# Sensy_Boi_sch.net
KiCad netlist of a schematic drawn in Altium Designer
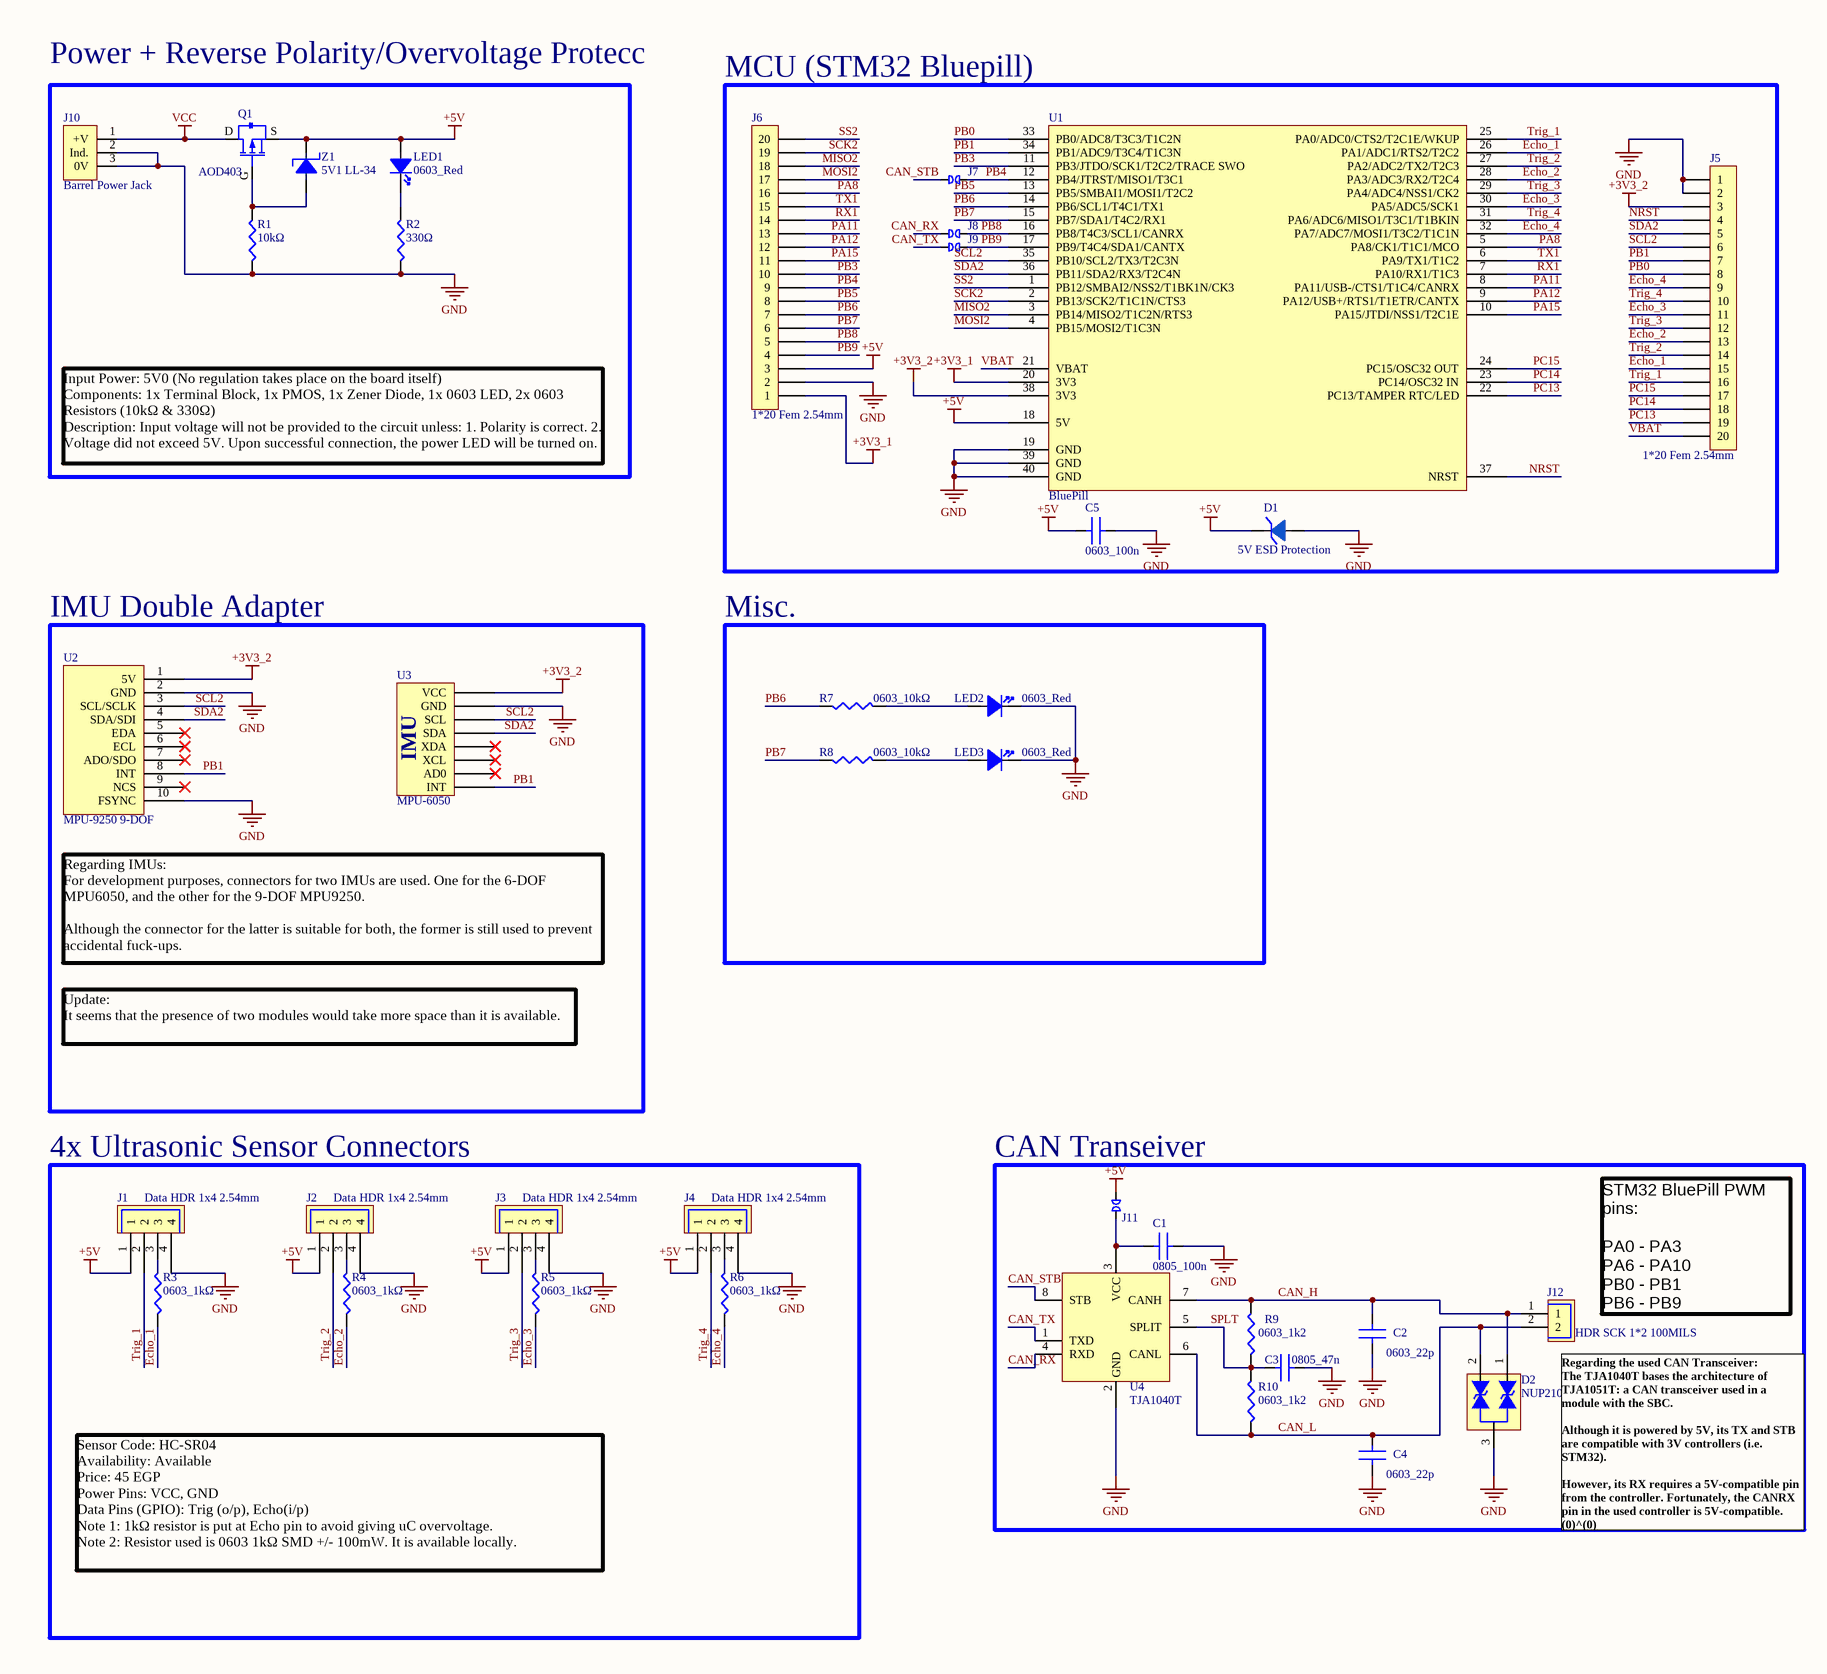
[diagram p0: Sensy_Boi_sch.SchDoc, left]

(export (version "E")
  (design (tool "Eeschema 10.0.6"))
  (components
    (comp (ref "C1")
      (value "0805_100n")
      (footprint "C0805 - 0.1uf")
      (fields (field (name "TOLERANCE") "10%") (field (name "VOLTAGE") "25V"))
      (libsource (lib "TimerSMD_Components") (part "C2012X5R1E105K125AA"))
    )
    (comp (ref "C2")
      (value "0603_22p")
      (footprint "0603_CAP")
      (libsource (lib "TimerSMD_Components") (part "0603 Capacitor"))
    )
    (comp (ref "C3")
      (value "0805_47n")
      (footprint "C0805 - 0.1uf")
      (fields (field (name "TOLERANCE") "10%") (field (name "VOLTAGE") "25V"))
      (libsource (lib "TimerSMD_Components") (part "C2012X5R1E105K125AA"))
    )
    (comp (ref "C4")
      (value "0603_22p")
      (footprint "0603_CAP")
      (libsource (lib "TimerSMD_Components") (part "0603 Capacitor"))
    )
    (comp (ref "C5")
      (value "0603_100n")
      (footprint "0603_CAP")
      (libsource (lib "TimerSMD_Components") (part "0603 Capacitor"))
    )
    (comp (ref "D1")
      (value "5V ESD Protection")
      (footprint "D0-214AA")
      (libsource (lib "TimerSMD_Components") (part "SMBJ5.0A"))
    )
    (comp (ref "D2")
      (value "NUP2105L")
      (footprint "SO-23")
      (description "ESD Protection Dual Diode for CAN Bus Line Protection")
      (libsource (lib "TimerSMD_Components") (part "NUP2105L"))
    )
    (comp (ref "J1")
      (value "Data HDR 1x4 2.54mm")
      (footprint "DHDR_1x4_2.54mm")
      (description "MTA-100 Series, 2.54mm Pitch 4 Way 1 RowStraight PCB Header, Solder Term, 5A")
      (libsource (lib "CAD_Symbols") (part "4-Pin Data Connector"))
    )
    (comp (ref "J2")
      (value "Data HDR 1x4 2.54mm")
      (footprint "DHDR_1x4_2.54mm")
      (description "MTA-100 Series, 2.54mm Pitch 4 Way 1 RowStraight PCB Header, Solder Term, 5A")
      (libsource (lib "CAD_Symbols") (part "4-Pin Data Connector"))
    )
    (comp (ref "J3")
      (value "Data HDR 1x4 2.54mm")
      (footprint "DHDR_1x4_2.54mm")
      (description "MTA-100 Series, 2.54mm Pitch 4 Way 1 RowStraight PCB Header, Solder Term, 5A")
      (libsource (lib "CAD_Symbols") (part "4-Pin Data Connector"))
    )
    (comp (ref "J4")
      (value "Data HDR 1x4 2.54mm")
      (footprint "DHDR_1x4_2.54mm")
      (description "MTA-100 Series, 2.54mm Pitch 4 Way 1 RowStraight PCB Header, Solder Term, 5A")
      (libsource (lib "CAD_Symbols") (part "4-Pin Data Connector"))
    )
    (comp (ref "J5")
      (value "1*20 Fem 2.54mm")
      (footprint "20*1 FEM 2.54mm")
      (libsource (lib "") (part "1*20 Fem 2.54mm_1"))
    )
    (comp (ref "J6")
      (value "1*20 Fem 2.54mm")
      (footprint "20*1 FEM 2.54mm")
      (libsource (lib "CAD_Symbols") (part "1*20 Fem 2.54mm"))
    )
    (comp (ref "J7")
      (value "Jumper Pads")
      (footprint "JMP")
      (libsource (lib "TimerSMD_Components") (part "Jumper Pads"))
    )
    (comp (ref "J8")
      (value "Jumper Pads")
      (footprint "JMP")
      (libsource (lib "TimerSMD_Components") (part "Jumper Pads"))
    )
    (comp (ref "J9")
      (value "Jumper Pads")
      (footprint "JMP")
      (libsource (lib "TimerSMD_Components") (part "Jumper Pads"))
    )
    (comp (ref "J10")
      (value "Barrel Power Jack")
      (footprint "pwr_Jack")
      (description "DC-Power Socket 12V 5A 2, 1mm Solder Eyel")
      (libsource (lib "CAD_Symbols") (part "Con-Jack"))
    )
    (comp (ref "J11")
      (value "Jumper Pads")
      (footprint "JMP")
      (libsource (lib "TimerSMD_Components") (part "Jumper Pads"))
    )
    (comp (ref "J12")
      (value "HDR SCK 1*2 100MILS")
      (footprint "DHDR 1*2 2,54MM")
      (description "Conn Shrouded Header HDR 2 POS 2.54mm Solder ST Thru-Hole")
      (libsource (lib "CAD_Symbols") (part "2-Pin Data Connector"))
    )
    (comp (ref "LED1")
      (value "0603_Red")
      (footprint "0603_LED")
      (libsource (lib "TimerSMD_Components") (part "0603LED"))
    )
    (comp (ref "LED2")
      (value "0603_Red")
      (footprint "0603_LED")
      (libsource (lib "TimerSMD_Components") (part "0603LED"))
    )
    (comp (ref "LED3")
      (value "0603_Red")
      (footprint "0603_LED")
      (libsource (lib "TimerSMD_Components") (part "0603LED"))
    )
    (comp (ref "Q1")
      (value "AOD403")
      (footprint "DPAK")
      (description "MOSFET Transistor P-Channel 30V 15A 3.5V @ 250uA 6mΩ @ 20A,20V 2.5W TO-252-2(DPAK)")
      (libsource (lib "TimerSMD_Components") (part "AOD403"))
    )
    (comp (ref "R1")
      (value "10kΩ")
      (footprint "0603_CAP")
      (libsource (lib "TimerSMD_Components") (part "0603 Resistor"))
    )
    (comp (ref "R2")
      (value "330Ω")
      (footprint "0603_CAP")
      (libsource (lib "TimerSMD_Components") (part "0603 Resistor"))
    )
    (comp (ref "R3")
      (value "0603_1kΩ")
      (footprint "0603_CAP")
      (description "1k +/- 1 100mW")
      (libsource (lib "TimerSMD_Components") (part "0603 Resistor"))
    )
    (comp (ref "R4")
      (value "0603_1kΩ")
      (footprint "0603_CAP")
      (description "1k +/- 1 100mW")
      (libsource (lib "TimerSMD_Components") (part "0603 Resistor"))
    )
    (comp (ref "R5")
      (value "0603_1kΩ")
      (footprint "0603_CAP")
      (description "1k +/- 1 100mW")
      (libsource (lib "TimerSMD_Components") (part "0603 Resistor"))
    )
    (comp (ref "R6")
      (value "0603_1kΩ")
      (footprint "0603_CAP")
      (description "1k +/- 1 100mW")
      (libsource (lib "TimerSMD_Components") (part "0603 Resistor"))
    )
    (comp (ref "R7")
      (value "0603_10kΩ")
      (footprint "0603_CAP")
      (libsource (lib "TimerSMD_Components") (part "0603 Resistor"))
    )
    (comp (ref "R8")
      (value "0603_10kΩ")
      (footprint "0603_CAP")
      (libsource (lib "TimerSMD_Components") (part "0603 Resistor"))
    )
    (comp (ref "R9")
      (value "0603_1k2")
      (footprint "0603_CAP")
      (libsource (lib "TimerSMD_Components") (part "0603 Resistor"))
    )
    (comp (ref "R10")
      (value "0603_1k2")
      (footprint "0603_CAP")
      (libsource (lib "TimerSMD_Components") (part "0603 Resistor"))
    )
    (comp (ref "U1")
      (value "BluePill")
      (footprint "BluePill")
      (libsource (lib "CAD_Symbols") (part "STM32 BluePill"))
    )
    (comp (ref "U2")
      (value "MPU-9250 9-DOF")
      (footprint "MPU9250")
      (libsource (lib "CAD_Symbols") (part "MPU-9250 IMU"))
    )
    (comp (ref "U3")
      (value "MPU-6050")
      (footprint "IMU")
      (libsource (lib "CAD_Symbols") (part "MPU-6050 IMU"))
    )
    (comp (ref "U4")
      (value "TJA1040T")
      (footprint "SOP8 - duplicate")
      (description "CAN Transceiver")
      (libsource (lib "TimerSMD_Components") (part "TJA1040T"))
    )
    (comp (ref "Z1")
      (value "5V1 LL-34")
      (footprint "LL-34")
      (libsource (lib "TimerSMD_Components") (part "Zener 5V1 LL-34"))
    )
  )
  (nets
    (net (code "1") (name "+3V3_1") (class "Default")
      (node (ref "J6") (pin "1") (pinfunction "1_1") (pintype "passive"))
      (node (ref "U1") (pin "20") (pinfunction "3V3_20") (pintype "passive"))
    )
    (net (code "2") (name "+3V3_2") (class "Default")
      (node (ref "J5") (pin "3") (pinfunction "3_3") (pintype "passive"))
      (node (ref "U1") (pin "38") (pinfunction "3V3_38") (pintype "passive"))
      (node (ref "U2") (pin "1") (pinfunction "5V_1") (pintype "passive"))
      (node (ref "U3") (pin "VCC") (pinfunction "VCC_VCC") (pintype "passive"))
    )
    (net (code "3") (name "+5V") (class "Default")
      (node (ref "C5") (pin "1") (pinfunction "1_1") (pintype "passive"))
      (node (ref "D1") (pin "K") (pinfunction "Cathode_K") (pintype "passive"))
      (node (ref "J1") (pin "1") (pinfunction "1_1") (pintype "passive"))
      (node (ref "J11") (pin "2") (pinfunction "2_2") (pintype "passive"))
      (node (ref "J2") (pin "1") (pinfunction "1_1") (pintype "passive"))
      (node (ref "J3") (pin "1") (pinfunction "1_1") (pintype "passive"))
      (node (ref "J4") (pin "1") (pinfunction "1_1") (pintype "passive"))
      (node (ref "J6") (pin "3") (pinfunction "3_3") (pintype "passive"))
      (node (ref "LED1") (pin "1") (pinfunction "Anode_1") (pintype "passive"))
      (node (ref "Q1") (pin "S") (pinfunction "S_S") (pintype "passive"))
      (node (ref "U1") (pin "18") (pinfunction "5V_18") (pintype "passive"))
      (node (ref "Z1") (pin "K") (pinfunction "Cathode_K") (pintype "passive"))
    )
    (net (code "4") (name "/CAN_H") (class "Default")
      (node (ref "C2") (pin "2") (pinfunction "2_2") (pintype "passive"))
      (node (ref "D2") (pin "1") (pinfunction "IN1_1") (pintype "passive"))
      (node (ref "J12") (pin "1") (pinfunction "1_1") (pintype "passive"))
      (node (ref "R9") (pin "2") (pinfunction "2_2") (pintype "passive"))
      (node (ref "U4") (pin "7") (pinfunction "CANH_7") (pintype "passive"))
    )
    (net (code "5") (name "/CAN_L") (class "Default")
      (node (ref "C4") (pin "2") (pinfunction "2_2") (pintype "passive"))
      (node (ref "D2") (pin "2") (pinfunction "IN2_2") (pintype "passive"))
      (node (ref "J12") (pin "2") (pinfunction "2_2") (pintype "passive"))
      (node (ref "R10") (pin "1") (pinfunction "1_1") (pintype "passive"))
      (node (ref "U4") (pin "6") (pinfunction "CANL_6") (pintype "passive"))
    )
    (net (code "6") (name "/CAN_RX") (class "Default")
      (node (ref "J8") (pin "1") (pinfunction "1_1") (pintype "passive"))
      (node (ref "U4") (pin "4") (pinfunction "RXD_4") (pintype "passive"))
    )
    (net (code "7") (name "/CAN_STB") (class "Default")
      (node (ref "J7") (pin "1") (pinfunction "1_1") (pintype "passive"))
      (node (ref "U4") (pin "8") (pinfunction "STB_8") (pintype "passive"))
    )
    (net (code "8") (name "/CAN_TX") (class "Default")
      (node (ref "J9") (pin "1") (pinfunction "1_1") (pintype "passive"))
      (node (ref "U4") (pin "1") (pinfunction "TXD_1") (pintype "passive"))
    )
    (net (code "9") (name "/Echo_1") (class "Default")
      (node (ref "J5") (pin "15") (pinfunction "15_15") (pintype "passive"))
      (node (ref "R3") (pin "1") (pinfunction "1_1") (pintype "passive"))
      (node (ref "U1") (pin "26") (pinfunction "PA1/ADC1/RTS2/T2C2_26") (pintype "passive"))
    )
    (net (code "10") (name "/Echo_2") (class "Default")
      (node (ref "J5") (pin "13") (pinfunction "13_13") (pintype "passive"))
      (node (ref "R4") (pin "1") (pinfunction "1_1") (pintype "passive"))
      (node (ref "U1") (pin "28") (pinfunction "PA3/ADC3/RX2/T2C4_28") (pintype "passive"))
    )
    (net (code "11") (name "/Echo_3") (class "Default")
      (node (ref "J5") (pin "11") (pinfunction "11_11") (pintype "passive"))
      (node (ref "R5") (pin "1") (pinfunction "1_1") (pintype "passive"))
      (node (ref "U1") (pin "30") (pinfunction "PA5/ADC5/SCK1_30") (pintype "passive"))
    )
    (net (code "12") (name "/Echo_4") (class "Default")
      (node (ref "J5") (pin "9") (pinfunction "9_9") (pintype "passive"))
      (node (ref "R6") (pin "1") (pinfunction "1_1") (pintype "passive"))
      (node (ref "U1") (pin "32") (pinfunction "PA7/ADC7/MOSI1/T3C2/T1C1N_32") (pintype "passive"))
    )
    (net (code "13") (name "/MISO2") (class "Default")
      (node (ref "J6") (pin "18") (pinfunction "18_18") (pintype "passive"))
      (node (ref "U1") (pin "3") (pinfunction "PB14/MISO2/T1C2N/RTS3_3") (pintype "passive"))
    )
    (net (code "14") (name "/MOSI2") (class "Default")
      (node (ref "J6") (pin "17") (pinfunction "17_17") (pintype "passive"))
      (node (ref "U1") (pin "4") (pinfunction "PB15/MOSI2/T1C3N_4") (pintype "passive"))
    )
    (net (code "15") (name "/NRST") (class "Default")
      (node (ref "J5") (pin "4") (pinfunction "4_4") (pintype "passive"))
      (node (ref "U1") (pin "37") (pinfunction "NRST_37") (pintype "passive"))
    )
    (net (code "16") (name "/PA8") (class "Default")
      (node (ref "J6") (pin "16") (pinfunction "16_16") (pintype "passive"))
      (node (ref "U1") (pin "5") (pinfunction "PA8/CK1/T1C1/MCO_5") (pintype "passive"))
    )
    (net (code "17") (name "/PA11") (class "Default")
      (node (ref "J6") (pin "13") (pinfunction "13_13") (pintype "passive"))
      (node (ref "U1") (pin "8") (pinfunction "PA11/USB-/CTS1/T1C4/CANRX_8") (pintype "passive"))
    )
    (net (code "18") (name "/PA12") (class "Default")
      (node (ref "J6") (pin "12") (pinfunction "12_12") (pintype "passive"))
      (node (ref "U1") (pin "9") (pinfunction "PA12/USB+/RTS1/T1ETR/CANTX_9") (pintype "passive"))
    )
    (net (code "19") (name "/PA15") (class "Default")
      (node (ref "J6") (pin "11") (pinfunction "11_11") (pintype "passive"))
      (node (ref "U1") (pin "10") (pinfunction "PA15/JTDI/NSS1/T2C1E_10") (pintype "passive"))
    )
    (net (code "20") (name "/PB0") (class "Default")
      (node (ref "J5") (pin "8") (pinfunction "8_8") (pintype "passive"))
      (node (ref "U1") (pin "33") (pinfunction "PB0/ADC8/T3C3/T1C2N_33") (pintype "passive"))
    )
    (net (code "21") (name "/PB1") (class "Default")
      (node (ref "J5") (pin "7") (pinfunction "7_7") (pintype "passive"))
      (node (ref "U1") (pin "34") (pinfunction "PB1/ADC9/T3C4/T1C3N_34") (pintype "passive"))
      (node (ref "U2") (pin "8") (pinfunction "INT_8") (pintype "passive"))
      (node (ref "U3") (pin "INT") (pinfunction "INT_INT") (pintype "passive"))
    )
    (net (code "22") (name "/PB3") (class "Default")
      (node (ref "J6") (pin "10") (pinfunction "10_10") (pintype "passive"))
      (node (ref "U1") (pin "11") (pinfunction "PB3/JTDO/SCK1/T2C2/TRACE_SWO_11") (pintype "passive"))
    )
    (net (code "23") (name "/PB4") (class "Default")
      (node (ref "J6") (pin "9") (pinfunction "9_9") (pintype "passive"))
      (node (ref "J7") (pin "2") (pinfunction "2_2") (pintype "passive"))
      (node (ref "U1") (pin "12") (pinfunction "PB4/JTRST/MISO1/T3C1_12") (pintype "passive"))
    )
    (net (code "24") (name "/PB5") (class "Default")
      (node (ref "J6") (pin "8") (pinfunction "8_8") (pintype "passive"))
      (node (ref "U1") (pin "13") (pinfunction "PB5/SMBAI1/MOSI1/T2C2_13") (pintype "passive"))
    )
    (net (code "25") (name "/PB6") (class "Default")
      (node (ref "J6") (pin "7") (pinfunction "7_7") (pintype "passive"))
      (node (ref "R7") (pin "2") (pinfunction "2_2") (pintype "passive"))
      (node (ref "U1") (pin "14") (pinfunction "PB6/SCL1/T4C1/TX1_14") (pintype "passive"))
    )
    (net (code "26") (name "/PB7") (class "Default")
      (node (ref "J6") (pin "6") (pinfunction "6_6") (pintype "passive"))
      (node (ref "R8") (pin "2") (pinfunction "2_2") (pintype "passive"))
      (node (ref "U1") (pin "15") (pinfunction "PB7/SDA1/T4C2/RX1_15") (pintype "passive"))
    )
    (net (code "27") (name "/PB8") (class "Default")
      (node (ref "J6") (pin "5") (pinfunction "5_5") (pintype "passive"))
      (node (ref "J8") (pin "2") (pinfunction "2_2") (pintype "passive"))
      (node (ref "U1") (pin "16") (pinfunction "PB8/T4C3/SCL1/CANRX_16") (pintype "passive"))
    )
    (net (code "28") (name "/PB9") (class "Default")
      (node (ref "J6") (pin "4") (pinfunction "4_4") (pintype "passive"))
      (node (ref "J9") (pin "2") (pinfunction "2_2") (pintype "passive"))
      (node (ref "U1") (pin "17") (pinfunction "PB9/T4C4/SDA1/CANTX_17") (pintype "passive"))
    )
    (net (code "29") (name "/PC13") (class "Default")
      (node (ref "J5") (pin "19") (pinfunction "19_19") (pintype "passive"))
      (node (ref "U1") (pin "22") (pinfunction "PC13/TAMPER_RTC/LED_22") (pintype "passive"))
    )
    (net (code "30") (name "/PC14") (class "Default")
      (node (ref "J5") (pin "18") (pinfunction "18_18") (pintype "passive"))
      (node (ref "U1") (pin "23") (pinfunction "PC14/OSC32_IN_23") (pintype "passive"))
    )
    (net (code "31") (name "/PC15") (class "Default")
      (node (ref "J5") (pin "17") (pinfunction "17_17") (pintype "passive"))
      (node (ref "U1") (pin "24") (pinfunction "PC15/OSC32_OUT_24") (pintype "passive"))
    )
    (net (code "32") (name "/RX1") (class "Default")
      (node (ref "J6") (pin "14") (pinfunction "14_14") (pintype "passive"))
      (node (ref "U1") (pin "7") (pinfunction "PA10/RX1/T1C3_7") (pintype "passive"))
    )
    (net (code "33") (name "/SCK2") (class "Default")
      (node (ref "J6") (pin "19") (pinfunction "19_19") (pintype "passive"))
      (node (ref "U1") (pin "2") (pinfunction "PB13/SCK2/T1C1N/CTS3_2") (pintype "passive"))
    )
    (net (code "34") (name "/SCL2") (class "Default")
      (node (ref "J5") (pin "6") (pinfunction "6_6") (pintype "passive"))
      (node (ref "U1") (pin "35") (pinfunction "PB10/SCL2/TX3/T2C3N_35") (pintype "passive"))
      (node (ref "U2") (pin "3") (pinfunction "SCL/SCLK_3") (pintype "passive"))
      (node (ref "U3") (pin "SCL") (pinfunction "SCL_SCL") (pintype "passive"))
    )
    (net (code "35") (name "/SDA2") (class "Default")
      (node (ref "J5") (pin "5") (pinfunction "5_5") (pintype "passive"))
      (node (ref "U1") (pin "36") (pinfunction "PB11/SDA2/RX3/T2C4N_36") (pintype "passive"))
      (node (ref "U2") (pin "4") (pinfunction "SDA/SDI_4") (pintype "passive"))
      (node (ref "U3") (pin "SDA") (pinfunction "SDA_SDA") (pintype "passive"))
    )
    (net (code "36") (name "/SPLT") (class "Default")
      (node (ref "C3") (pin "2") (pinfunction "2_2") (pintype "passive"))
      (node (ref "R10") (pin "2") (pinfunction "2_2") (pintype "passive"))
      (node (ref "R9") (pin "1") (pinfunction "1_1") (pintype "passive"))
      (node (ref "U4") (pin "5") (pinfunction "SPLIT_5") (pintype "passive"))
    )
    (net (code "37") (name "/SS2") (class "Default")
      (node (ref "J6") (pin "20") (pinfunction "20_20") (pintype "passive"))
      (node (ref "U1") (pin "1") (pinfunction "PB12/SMBAI2/NSS2/T1BK1N/CK3_1") (pintype "passive"))
    )
    (net (code "38") (name "/TX1") (class "Default")
      (node (ref "J6") (pin "15") (pinfunction "15_15") (pintype "passive"))
      (node (ref "U1") (pin "6") (pinfunction "PA9/TX1/T1C2_6") (pintype "passive"))
    )
    (net (code "39") (name "/Trig_1") (class "Default")
      (node (ref "J1") (pin "2") (pinfunction "2_2") (pintype "passive"))
      (node (ref "J5") (pin "16") (pinfunction "16_16") (pintype "passive"))
      (node (ref "U1") (pin "25") (pinfunction "PA0/ADC0/CTS2/T2C1E/WKUP_25") (pintype "passive"))
    )
    (net (code "40") (name "/Trig_2") (class "Default")
      (node (ref "J2") (pin "2") (pinfunction "2_2") (pintype "passive"))
      (node (ref "J5") (pin "14") (pinfunction "14_14") (pintype "passive"))
      (node (ref "U1") (pin "27") (pinfunction "PA2/ADC2/TX2/T2C3_27") (pintype "passive"))
    )
    (net (code "41") (name "/Trig_3") (class "Default")
      (node (ref "J3") (pin "2") (pinfunction "2_2") (pintype "passive"))
      (node (ref "J5") (pin "12") (pinfunction "12_12") (pintype "passive"))
      (node (ref "U1") (pin "29") (pinfunction "PA4/ADC4/NSS1/CK2_29") (pintype "passive"))
    )
    (net (code "42") (name "/Trig_4") (class "Default")
      (node (ref "J4") (pin "2") (pinfunction "2_2") (pintype "passive"))
      (node (ref "J5") (pin "10") (pinfunction "10_10") (pintype "passive"))
      (node (ref "U1") (pin "31") (pinfunction "PA6/ADC6/MISO1/T3C1/T1BKIN_31") (pintype "passive"))
    )
    (net (code "43") (name "/VBAT") (class "Default")
      (node (ref "J5") (pin "20") (pinfunction "20_20") (pintype "passive"))
      (node (ref "U1") (pin "21") (pinfunction "VBAT_21") (pintype "passive"))
    )
    (net (code "44") (name "GND") (class "Default")
      (node (ref "C1") (pin "1") (pinfunction "1_1") (pintype "passive"))
      (node (ref "C2") (pin "1") (pinfunction "1_1") (pintype "passive"))
      (node (ref "C3") (pin "1") (pinfunction "1_1") (pintype "passive"))
      (node (ref "C4") (pin "1") (pinfunction "1_1") (pintype "passive"))
      (node (ref "C5") (pin "2") (pinfunction "2_2") (pintype "passive"))
      (node (ref "D1") (pin "A") (pinfunction "Anode_A") (pintype "passive"))
      (node (ref "D2") (pin "3") (pinfunction "IN3_3") (pintype "passive"))
      (node (ref "J1") (pin "4") (pinfunction "4_4") (pintype "passive"))
      (node (ref "J10") (pin "2") (pinfunction "Ind._2") (pintype "passive"))
      (node (ref "J10") (pin "3") (pinfunction "_0V_3") (pintype "passive"))
      (node (ref "J2") (pin "4") (pinfunction "4_4") (pintype "passive"))
      (node (ref "J3") (pin "4") (pinfunction "4_4") (pintype "passive"))
      (node (ref "J4") (pin "4") (pinfunction "4_4") (pintype "passive"))
      (node (ref "J5") (pin "1") (pinfunction "1_1") (pintype "passive"))
      (node (ref "J5") (pin "2") (pinfunction "2_2") (pintype "passive"))
      (node (ref "J6") (pin "2") (pinfunction "2_2") (pintype "passive"))
      (node (ref "LED2") (pin "2") (pinfunction "Cathode_2") (pintype "passive"))
      (node (ref "LED3") (pin "2") (pinfunction "Cathode_2") (pintype "passive"))
      (node (ref "R1") (pin "1") (pinfunction "1_1") (pintype "passive"))
      (node (ref "R2") (pin "1") (pinfunction "1_1") (pintype "passive"))
      (node (ref "U1") (pin "19") (pinfunction "GND_19") (pintype "passive"))
      (node (ref "U1") (pin "39") (pinfunction "GND_39") (pintype "passive"))
      (node (ref "U1") (pin "40") (pinfunction "GND_40") (pintype "passive"))
      (node (ref "U2") (pin "10") (pinfunction "FSYNC_10") (pintype "passive"))
      (node (ref "U2") (pin "2") (pinfunction "GND_2") (pintype "passive"))
      (node (ref "U3") (pin "GND") (pinfunction "GND_GND") (pintype "passive"))
      (node (ref "U4") (pin "2") (pinfunction "GND_2") (pintype "passive"))
    )
    (net (code "45") (name "Net-(J1-Pad3)") (class "Default")
      (node (ref "J1") (pin "3") (pinfunction "3_3") (pintype "passive"))
      (node (ref "R3") (pin "2") (pinfunction "2_2") (pintype "passive"))
    )
    (net (code "46") (name "Net-(J2-Pad3)") (class "Default")
      (node (ref "J2") (pin "3") (pinfunction "3_3") (pintype "passive"))
      (node (ref "R4") (pin "2") (pinfunction "2_2") (pintype "passive"))
    )
    (net (code "47") (name "Net-(J3-Pad3)") (class "Default")
      (node (ref "J3") (pin "3") (pinfunction "3_3") (pintype "passive"))
      (node (ref "R5") (pin "2") (pinfunction "2_2") (pintype "passive"))
    )
    (net (code "48") (name "Net-(J4-Pad3)") (class "Default")
      (node (ref "J4") (pin "3") (pinfunction "3_3") (pintype "passive"))
      (node (ref "R6") (pin "2") (pinfunction "2_2") (pintype "passive"))
    )
    (net (code "49") (name "Net-(LED1-Cathode)") (class "Default")
      (node (ref "LED1") (pin "2") (pinfunction "Cathode_2") (pintype "passive"))
      (node (ref "R2") (pin "2") (pinfunction "2_2") (pintype "passive"))
    )
    (net (code "50") (name "Net-(LED2-Anode)") (class "Default")
      (node (ref "LED2") (pin "1") (pinfunction "Anode_1") (pintype "passive"))
      (node (ref "R7") (pin "1") (pinfunction "1_1") (pintype "passive"))
    )
    (net (code "51") (name "Net-(LED3-Anode)") (class "Default")
      (node (ref "LED3") (pin "1") (pinfunction "Anode_1") (pintype "passive"))
      (node (ref "R8") (pin "1") (pinfunction "1_1") (pintype "passive"))
    )
    (net (code "52") (name "Net-(U4-VCC)") (class "Default")
      (node (ref "C1") (pin "2") (pinfunction "2_2") (pintype "passive"))
      (node (ref "J11") (pin "1") (pinfunction "1_1") (pintype "passive"))
      (node (ref "U4") (pin "3") (pinfunction "VCC_3") (pintype "passive"))
    )
    (net (code "53") (name "Net-(Z1-Anode)") (class "Default")
      (node (ref "Q1") (pin "G") (pinfunction "G_G") (pintype "passive"))
      (node (ref "R1") (pin "2") (pinfunction "2_2") (pintype "passive"))
      (node (ref "Z1") (pin "A") (pinfunction "Anode_A") (pintype "passive"))
    )
    (net (code "54") (name "VCC") (class "Default")
      (node (ref "J10") (pin "1") (pinfunction "+V_1") (pintype "passive"))
      (node (ref "Q1") (pin "D") (pinfunction "D_D") (pintype "passive"))
    )
    (net (code "55") (name "unconnected-(U2-ADO{slash}SDO-Pad7)") (class "Default")
      (node (ref "U2") (pin "7") (pinfunction "ADO/SDO_7") (pintype "passive+no_connect"))
    )
    (net (code "56") (name "unconnected-(U2-ECL-Pad6)") (class "Default")
      (node (ref "U2") (pin "6") (pinfunction "ECL_6") (pintype "passive+no_connect"))
    )
    (net (code "57") (name "unconnected-(U2-EDA-Pad5)") (class "Default")
      (node (ref "U2") (pin "5") (pinfunction "EDA_5") (pintype "passive+no_connect"))
    )
    (net (code "58") (name "unconnected-(U2-NCS-Pad9)") (class "Default")
      (node (ref "U2") (pin "9") (pinfunction "NCS_9") (pintype "passive+no_connect"))
    )
    (net (code "59") (name "unconnected-(U3-PadAD0)") (class "Default")
      (node (ref "U3") (pin "AD0") (pinfunction "AD0_AD0") (pintype "passive+no_connect"))
    )
    (net (code "60") (name "unconnected-(U3-PadXCL)") (class "Default")
      (node (ref "U3") (pin "XCL") (pinfunction "XCL_XCL") (pintype "passive+no_connect"))
    )
    (net (code "61") (name "unconnected-(U3-PadXDA)") (class "Default")
      (node (ref "U3") (pin "XDA") (pinfunction "XDA_XDA") (pintype "passive+no_connect"))
    )
  )
)
